# POWER.net
KiCad netlist of a schematic drawn in Altium Designer
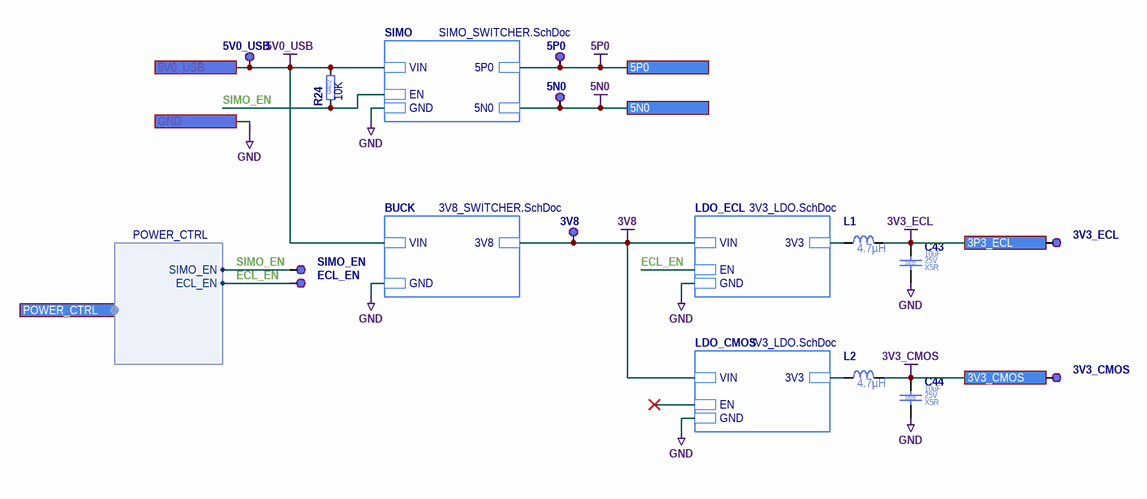
[diagram p0: POWER.SchDoc]

(export (version "E")
  (design (tool "Eeschema 10.0.6"))
  (components
    (comp (ref "3V3_CMOS")
      (value "TP_PAD_1.3MM")
      (footprint "TP_PAD_1.3MM")
      (description "Testpoint SMD 1.3mm")
      (libsource (lib "7Sigma") (part "TESTPOINT"))
    )
    (comp (ref "3V3_ECL")
      (value "TP_PAD_1.3MM")
      (footprint "TP_PAD_1.3MM")
      (description "Testpoint SMD 1.3mm")
      (libsource (lib "7Sigma") (part "TESTPOINT"))
    )
    (comp (ref "3V8")
      (value "TP_PAD_1.3MM")
      (footprint "TP_PAD_1.3MM")
      (description "Testpoint SMD 1.3mm")
      (libsource (lib "7Sigma") (part "TESTPOINT"))
    )
    (comp (ref "5N0")
      (value "TP_PAD_1.3MM")
      (footprint "TP_PAD_1.3MM")
      (description "Testpoint SMD 1.3mm")
      (libsource (lib "7Sigma") (part "TESTPOINT"))
    )
    (comp (ref "5P0")
      (value "TP_PAD_1.3MM")
      (footprint "TP_PAD_1.3MM")
      (description "Testpoint SMD 1.3mm")
      (libsource (lib "7Sigma") (part "TESTPOINT"))
    )
    (comp (ref "5V0_USB")
      (value "TP_PAD_1.3MM")
      (footprint "TP_PAD_1.3MM")
      (description "Testpoint SMD 1.3mm")
      (libsource (lib "7Sigma") (part "TESTPOINT"))
    )
    (comp (ref "C43")
      (value "C_10UF_25V_X5R_0805_10")
      (footprint "C_0805_2012")
      (description "Ceramic Capacitor")
      (fields
        (field (name "CASE/PACKAGE") "0805")
        (field (name "VOLTAGE RATING (DC)") "25V")
        (field (name "DIELECTRIC") "X5R")
        (field (name "CAPACITANCE") "10uF")
        (field (name "TOLERANCE") "10%")
        (field (name "MANUFACTURER PART NUMBER") "CL21A106KAYNNNE")
      )
      (libsource (lib "7Sigma") (part "C"))
    )
    (comp (ref "C44")
      (value "C_10UF_25V_X5R_0805_10")
      (footprint "C_0805_2012")
      (description "Ceramic Capacitor")
      (fields
        (field (name "CASE/PACKAGE") "0805")
        (field (name "VOLTAGE RATING (DC)") "25V")
        (field (name "DIELECTRIC") "X5R")
        (field (name "CAPACITANCE") "10uF")
        (field (name "TOLERANCE") "10%")
        (field (name "MANUFACTURER PART NUMBER") "CL21A106KAYNNNE")
      )
      (libsource (lib "7Sigma") (part "C"))
    )
    (comp (ref "ECL_EN")
      (value "TP_PAD_1.3MM")
      (footprint "TP_PAD_1.3MM")
      (description "Testpoint SMD 1.3mm")
      (libsource (lib "7Sigma") (part "TESTPOINT"))
    )
    (comp (ref "L1")
      (value "1239AS-H-4R7M=P2")
      (footprint "L_1008_2520")
      (description "Power Inductor")
      (fields
        (field (name "INDUCTANCE") "4.7µH")
        (field (name "MANUFACTURER") "Murata Electronics")
        (field (name "TOLERANCE") "20%")
      )
      (libsource (lib "7Sigma") (part "L"))
    )
    (comp (ref "L2")
      (value "1239AS-H-4R7M=P2")
      (footprint "L_1008_2520")
      (description "Power Inductor")
      (fields
        (field (name "INDUCTANCE") "4.7µH")
        (field (name "MANUFACTURER") "Murata Electronics")
        (field (name "TOLERANCE") "20%")
      )
      (libsource (lib "7Sigma") (part "L"))
    )
    (comp (ref "R24")
      (value "R_10K_0402_1")
      (footprint "R_0402_1005")
      (description "Thick Film Resistor")
      (fields
        (field (name "RESISTANCE") "10K")
        (field (name "CASE/PACKAGE") "0402")
        (field (name "TOLERANCE") "1%")
        (field (name "MANUFACTURER") "Yageo")
      )
      (libsource (lib "7Sigma") (part "R"))
    )
    (comp (ref "SIMO_EN")
      (value "TP_PAD_1.3MM")
      (footprint "TP_PAD_1.3MM")
      (description "Testpoint SMD 1.3mm")
      (libsource (lib "7Sigma") (part "TESTPOINT"))
    )
  )
  (nets
    (net (code "2") (name "/3V3") (class "Default")
      (node (ref "L1") (pin "1") (pinfunction "1_1") (pintype "passive"))
    )
    (net (code "3") (name "/3V3_1") (class "Default")
      (node (ref "L2") (pin "1") (pinfunction "1_1") (pintype "passive"))
    )
    (net (code "4") (name "/ECL_EN") (class "Default")
      (node (ref "ECL_EN") (pin "1") (pinfunction "TP_1") (pintype "passive"))
    )
    (net (code "6") (name "/SIMO_EN") (class "Default")
      (node (ref "R24") (pin "1") (pinfunction "1_1") (pintype "passive"))
      (node (ref "SIMO_EN") (pin "1") (pinfunction "TP_1") (pintype "passive"))
    )
    (net (code "8") (name "3V3_CMOS") (class "Default")
      (node (ref "3V3_CMOS") (pin "1") (pinfunction "TP_1") (pintype "passive"))
      (node (ref "C44") (pin "1") (pinfunction "1_1") (pintype "passive"))
      (node (ref "L2") (pin "2") (pinfunction "2_2") (pintype "passive"))
    )
    (net (code "9") (name "3V3_ECL") (class "Default")
      (node (ref "3V3_ECL") (pin "1") (pinfunction "TP_1") (pintype "passive"))
      (node (ref "C43") (pin "1") (pinfunction "1_1") (pintype "passive"))
      (node (ref "L1") (pin "2") (pinfunction "2_2") (pintype "passive"))
    )
    (net (code "10") (name "3V8") (class "Default")
      (node (ref "3V8") (pin "1") (pinfunction "TP_1") (pintype "passive"))
    )
    (net (code "11") (name "5N0") (class "Default")
      (node (ref "5N0") (pin "1") (pinfunction "TP_1") (pintype "passive"))
    )
    (net (code "12") (name "5P0") (class "Default")
      (node (ref "5P0") (pin "1") (pinfunction "TP_1") (pintype "passive"))
    )
    (net (code "13") (name "5V0_USB") (class "Default")
      (node (ref "5V0_USB") (pin "1") (pinfunction "TP_1") (pintype "passive"))
      (node (ref "R24") (pin "2") (pinfunction "2_2") (pintype "passive"))
    )
    (net (code "14") (name "GND") (class "Default")
      (node (ref "C43") (pin "2") (pinfunction "2_2") (pintype "passive"))
      (node (ref "C44") (pin "2") (pinfunction "2_2") (pintype "passive"))
    )
  )
)
